# BlueESC.net
KiCad netlist of a schematic drawn in EAGLE
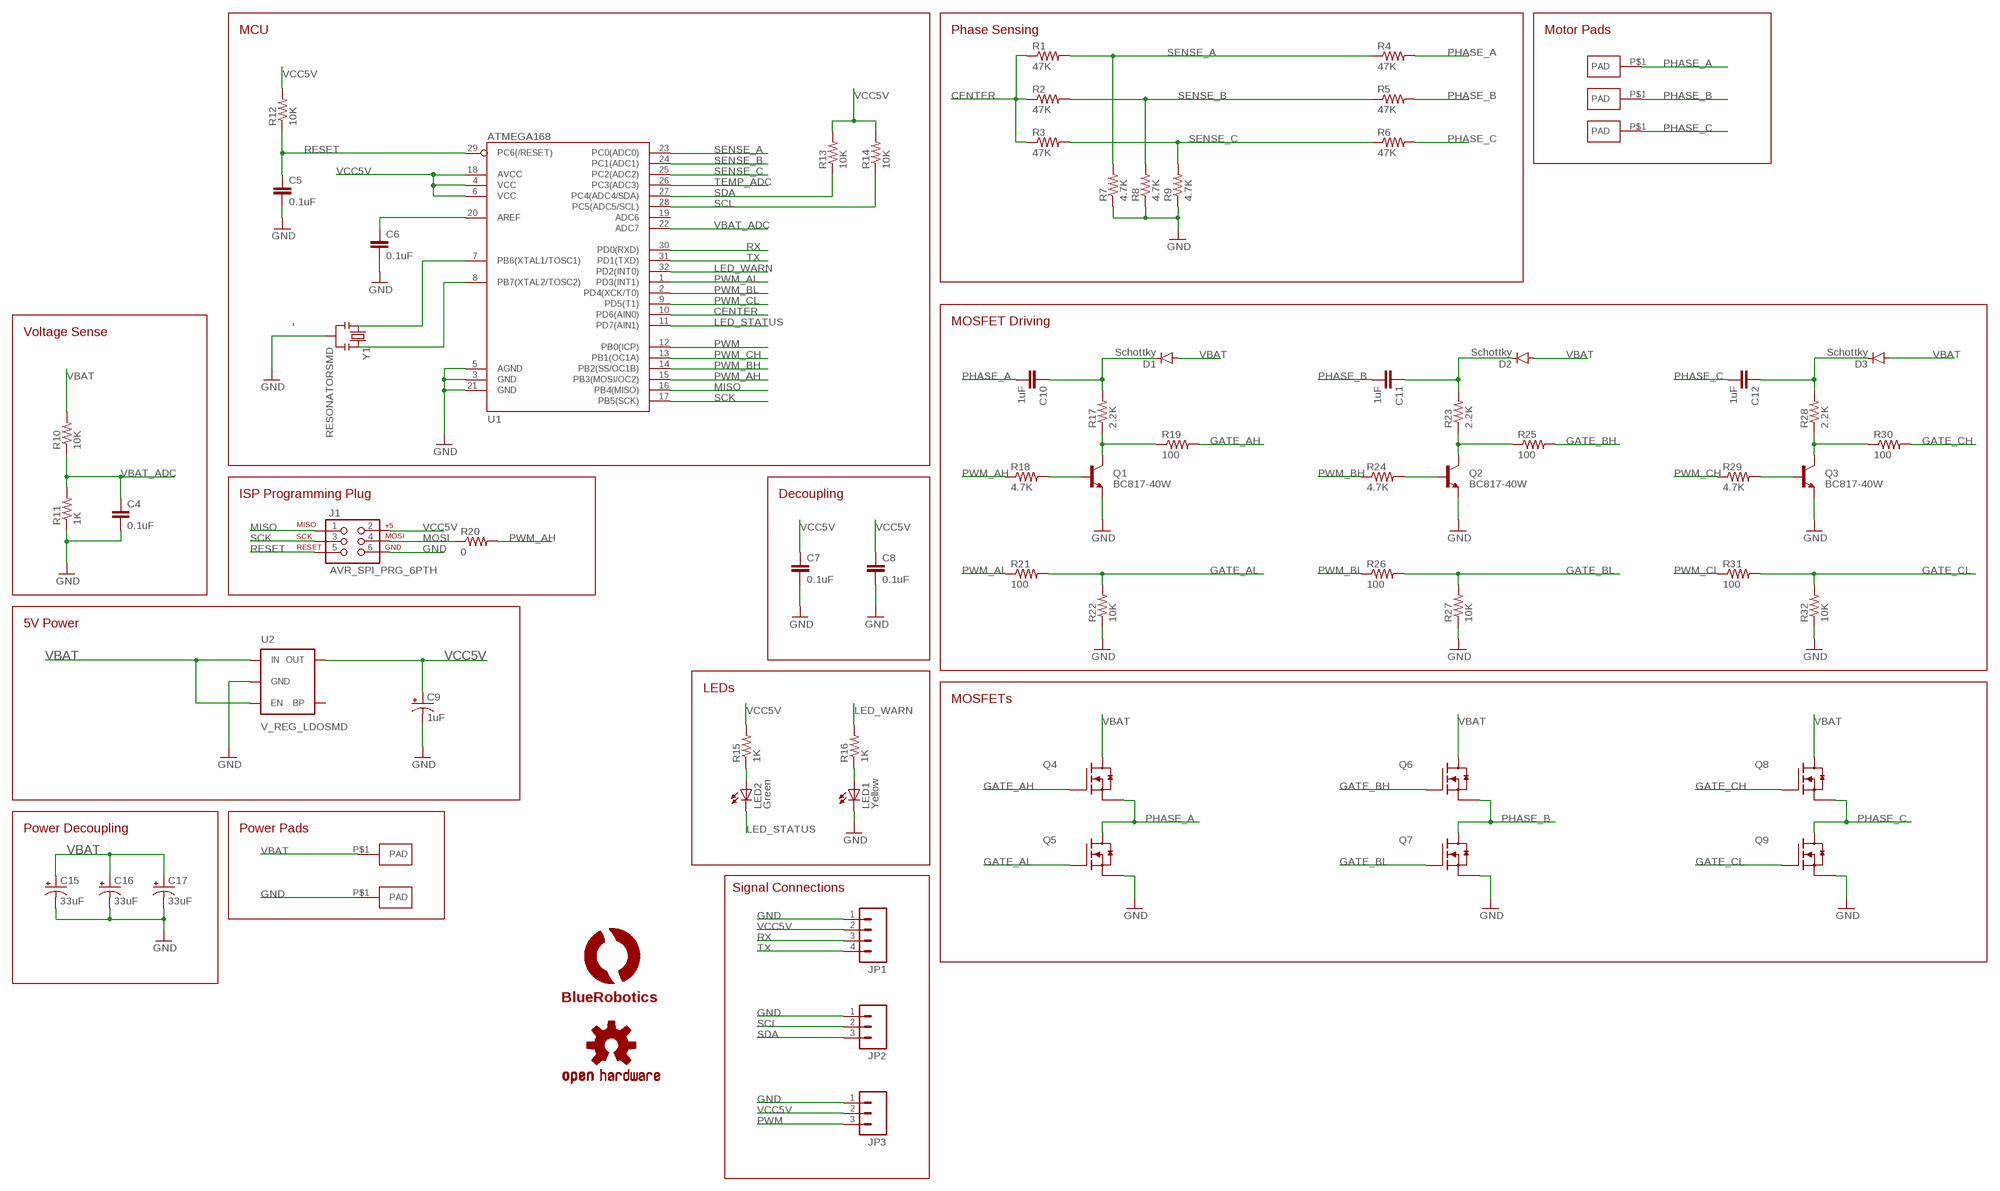
[diagram p0: schematic, sheet 1]

(export (version "E")
  (design (tool "Eeschema 10.0.6"))
  (components
    (comp (ref "C4")
      (value "0.1uF")
      (footprint "eagle-import:0603-CAP")
      (libsource (lib "eagle-import") (part "CAP0603-CAP"))
    )
    (comp (ref "C5")
      (value "0.1uF")
      (footprint "eagle-import:0603-CAP")
      (libsource (lib "eagle-import") (part "CAP0603-CAP"))
    )
    (comp (ref "C6")
      (value "0.1uF")
      (footprint "eagle-import:0603-CAP")
      (libsource (lib "eagle-import") (part "CAP0603-CAP"))
    )
    (comp (ref "C7")
      (value "0.1uF")
      (footprint "eagle-import:0603-CAP")
      (libsource (lib "eagle-import") (part "CAP0603-CAP"))
    )
    (comp (ref "C8")
      (value "0.1uF")
      (footprint "eagle-import:0603-CAP")
      (libsource (lib "eagle-import") (part "CAP0603-CAP"))
    )
    (comp (ref "C9")
      (value "1uF")
      (footprint "eagle-import:EIA3216")
      (libsource (lib "eagle-import") (part "CAP_POL1206"))
    )
    (comp (ref "C10")
      (value "1uF")
      (footprint "eagle-import:0805")
      (libsource (lib "eagle-import") (part "CAP0805"))
    )
    (comp (ref "C11")
      (value "1uF")
      (footprint "eagle-import:0805")
      (libsource (lib "eagle-import") (part "CAP0805"))
    )
    (comp (ref "C12")
      (value "1uF")
      (footprint "eagle-import:0805")
      (libsource (lib "eagle-import") (part "CAP0805"))
    )
    (comp (ref "C15")
      (value "33uF")
      (footprint "eagle-import:EIA6032")
      (libsource (lib "eagle-import") (part "CAP_POL6032"))
    )
    (comp (ref "C16")
      (value "33uF")
      (footprint "eagle-import:EIA6032")
      (libsource (lib "eagle-import") (part "CAP_POL6032"))
    )
    (comp (ref "C17")
      (value "33uF")
      (footprint "eagle-import:EIA6032")
      (libsource (lib "eagle-import") (part "CAP_POL6032"))
    )
    (comp (ref "D1")
      (value "Schottky")
      (footprint "eagle-import:SOD-323")
      (libsource (lib "eagle-import") (part "DIODESOD"))
    )
    (comp (ref "D2")
      (value "Schottky")
      (footprint "eagle-import:SOD-323")
      (libsource (lib "eagle-import") (part "DIODESOD"))
    )
    (comp (ref "D3")
      (value "Schottky")
      (footprint "eagle-import:SOD-323")
      (libsource (lib "eagle-import") (part "DIODESOD"))
    )
    (comp (ref "J1")
      (value "AVR_SPI_PRG_6PTH")
      (footprint "eagle-import:2X3")
      (libsource (lib "eagle-import") (part "AVR_SPI_PRG_6PTH"))
    )
    (comp (ref "JP1")
      (value "M04PTH")
      (footprint "eagle-import:1X04")
      (libsource (lib "eagle-import") (part "M04PTH"))
    )
    (comp (ref "JP2")
      (value "M03PTH")
      (footprint "eagle-import:1X03")
      (libsource (lib "eagle-import") (part "M03PTH"))
    )
    (comp (ref "JP3")
      (value "M03PTH")
      (footprint "eagle-import:1X03")
      (libsource (lib "eagle-import") (part "M03PTH"))
    )
    (comp (ref "LED1")
      (value "Yellow")
      (footprint "eagle-import:LED-0603")
      (libsource (lib "eagle-import") (part "LED0603"))
    )
    (comp (ref "LED2")
      (value "Green")
      (footprint "eagle-import:LED-0603")
      (libsource (lib "eagle-import") (part "LED0603"))
    )
    (comp (ref "LOGO1")
      (value "OSHW-LOGOM")
      (footprint "eagle-import:OSHW-LOGO-M")
      (libsource (lib "eagle-import") (part "OSHW-LOGOM"))
    )
    (comp (ref "Q1")
      (value "BC817-40W")
      (footprint "eagle-import:SOT23")
      (libsource (lib "eagle-import") (part "TRANSISTOR_NPNSOT23"))
    )
    (comp (ref "Q2")
      (value "BC817-40W")
      (footprint "eagle-import:SOT23")
      (libsource (lib "eagle-import") (part "TRANSISTOR_NPNSOT23"))
    )
    (comp (ref "Q3")
      (value "BC817-40W")
      (footprint "eagle-import:SOT23")
      (libsource (lib "eagle-import") (part "TRANSISTOR_NPNSOT23"))
    )
    (comp (ref "Q4")
      (value "SI7370")
      (footprint "eagle-import:POWERPAK-SO-08")
      (libsource (lib "eagle-import") (part "SI7370"))
    )
    (comp (ref "Q5")
      (value "SI7370")
      (footprint "eagle-import:POWERPAK-SO-08")
      (libsource (lib "eagle-import") (part "SI7370"))
    )
    (comp (ref "Q6")
      (value "SiR158DP")
      (footprint "eagle-import:POWERPAK-SO-08")
      (libsource (lib "eagle-import") (part "SI7370"))
    )
    (comp (ref "Q7")
      (value "SI7370")
      (footprint "eagle-import:POWERPAK-SO-08")
      (libsource (lib "eagle-import") (part "SI7370"))
    )
    (comp (ref "Q8")
      (value "SI7370")
      (footprint "eagle-import:POWERPAK-SO-08")
      (libsource (lib "eagle-import") (part "SI7370"))
    )
    (comp (ref "Q9")
      (value "SI7370")
      (footprint "eagle-import:POWERPAK-SO-08")
      (libsource (lib "eagle-import") (part "SI7370"))
    )
    (comp (ref "R1")
      (value "47K")
      (footprint "eagle-import:0603-RES")
      (libsource (lib "eagle-import") (part "33KOHM1/10W1%(0603)"))
    )
    (comp (ref "R2")
      (value "47K")
      (footprint "eagle-import:0603-RES")
      (libsource (lib "eagle-import") (part "33KOHM1/10W1%(0603)"))
    )
    (comp (ref "R3")
      (value "47K")
      (footprint "eagle-import:0603-RES")
      (libsource (lib "eagle-import") (part "33KOHM1/10W1%(0603)"))
    )
    (comp (ref "R4")
      (value "47K")
      (footprint "eagle-import:0603-RES")
      (libsource (lib "eagle-import") (part "33KOHM1/10W1%(0603)"))
    )
    (comp (ref "R5")
      (value "47K")
      (footprint "eagle-import:0603-RES")
      (libsource (lib "eagle-import") (part "33KOHM1/10W1%(0603)"))
    )
    (comp (ref "R6")
      (value "47K")
      (footprint "eagle-import:0603-RES")
      (libsource (lib "eagle-import") (part "33KOHM1/10W1%(0603)"))
    )
    (comp (ref "R7")
      (value "4.7K")
      (footprint "eagle-import:0603-RES")
      (libsource (lib "eagle-import") (part "RESISTOR0603"))
    )
    (comp (ref "R8")
      (value "4.7K")
      (footprint "eagle-import:0603-RES")
      (libsource (lib "eagle-import") (part "RESISTOR0603"))
    )
    (comp (ref "R9")
      (value "4.7K")
      (footprint "eagle-import:0603-RES")
      (libsource (lib "eagle-import") (part "RESISTOR0603"))
    )
    (comp (ref "R10")
      (value "10K")
      (footprint "eagle-import:0603-RES")
      (libsource (lib "eagle-import") (part "33KOHM1/10W1%(0603)"))
    )
    (comp (ref "R11")
      (value "1K")
      (footprint "eagle-import:0603-RES")
      (libsource (lib "eagle-import") (part "33KOHM1/10W1%(0603)"))
    )
    (comp (ref "R12")
      (value "10K")
      (footprint "eagle-import:0603-RES")
      (libsource (lib "eagle-import") (part "33KOHM1/10W1%(0603)"))
    )
    (comp (ref "R13")
      (value "10K")
      (footprint "eagle-import:0603-RES")
      (libsource (lib "eagle-import") (part "33KOHM1/10W1%(0603)"))
    )
    (comp (ref "R14")
      (value "10K")
      (footprint "eagle-import:0603-RES")
      (libsource (lib "eagle-import") (part "33KOHM1/10W1%(0603)"))
    )
    (comp (ref "R15")
      (value "1K")
      (footprint "eagle-import:0603-RES")
      (libsource (lib "eagle-import") (part "RESISTOR0603-RES"))
    )
    (comp (ref "R16")
      (value "1K")
      (footprint "eagle-import:0603-RES")
      (libsource (lib "eagle-import") (part "RESISTOR0603-RES"))
    )
    (comp (ref "R17")
      (value "2.2K")
      (footprint "eagle-import:0603-RES")
      (libsource (lib "eagle-import") (part "33KOHM1/10W1%(0603)"))
    )
    (comp (ref "R18")
      (value "4.7K")
      (footprint "eagle-import:0603-RES")
      (libsource (lib "eagle-import") (part "33KOHM1/10W1%(0603)"))
    )
    (comp (ref "R19")
      (value "100")
      (footprint "eagle-import:0603-RES")
      (libsource (lib "eagle-import") (part "33KOHM1/10W1%(0603)"))
    )
    (comp (ref "R20")
      (value "0")
      (footprint "eagle-import:0603-RES")
      (libsource (lib "eagle-import") (part "33KOHM1/10W1%(0603)"))
    )
    (comp (ref "R21")
      (value "100")
      (footprint "eagle-import:0603-RES")
      (libsource (lib "eagle-import") (part "33KOHM1/10W1%(0603)"))
    )
    (comp (ref "R22")
      (value "10K")
      (footprint "eagle-import:0603-RES")
      (libsource (lib "eagle-import") (part "33KOHM1/10W1%(0603)"))
    )
    (comp (ref "R23")
      (value "2.2K")
      (footprint "eagle-import:0603-RES")
      (libsource (lib "eagle-import") (part "33KOHM1/10W1%(0603)"))
    )
    (comp (ref "R24")
      (value "4.7K")
      (footprint "eagle-import:0603-RES")
      (libsource (lib "eagle-import") (part "33KOHM1/10W1%(0603)"))
    )
    (comp (ref "R25")
      (value "100")
      (footprint "eagle-import:0603-RES")
      (libsource (lib "eagle-import") (part "33KOHM1/10W1%(0603)"))
    )
    (comp (ref "R26")
      (value "100")
      (footprint "eagle-import:0603-RES")
      (libsource (lib "eagle-import") (part "33KOHM1/10W1%(0603)"))
    )
    (comp (ref "R27")
      (value "10K")
      (footprint "eagle-import:0603-RES")
      (libsource (lib "eagle-import") (part "33KOHM1/10W1%(0603)"))
    )
    (comp (ref "R28")
      (value "2.2K")
      (footprint "eagle-import:0603-RES")
      (libsource (lib "eagle-import") (part "33KOHM1/10W1%(0603)"))
    )
    (comp (ref "R29")
      (value "4.7K")
      (footprint "eagle-import:0603-RES")
      (libsource (lib "eagle-import") (part "33KOHM1/10W1%(0603)"))
    )
    (comp (ref "R30")
      (value "100")
      (footprint "eagle-import:0603-RES")
      (libsource (lib "eagle-import") (part "33KOHM1/10W1%(0603)"))
    )
    (comp (ref "R31")
      (value "100")
      (footprint "eagle-import:0603-RES")
      (libsource (lib "eagle-import") (part "33KOHM1/10W1%(0603)"))
    )
    (comp (ref "R32")
      (value "10K")
      (footprint "eagle-import:0603-RES")
      (libsource (lib "eagle-import") (part "33KOHM1/10W1%(0603)"))
    )
    (comp (ref "U$1")
      (value "PADLARGE-ONE-SIDE")
      (footprint "eagle-import:PAD-0.2X0.3-ONE-SIDE")
      (libsource (lib "eagle-import") (part "PADLARGE-ONE-SIDE"))
    )
    (comp (ref "U$2")
      (value "PADLARGE-ONE-SIDE")
      (footprint "eagle-import:PAD-0.2X0.3-ONE-SIDE")
      (libsource (lib "eagle-import") (part "PADLARGE-ONE-SIDE"))
    )
    (comp (ref "U$3")
      (value "PADLARGE-ONE-SIDE")
      (footprint "eagle-import:PAD-0.2X0.3-ONE-SIDE")
      (libsource (lib "eagle-import") (part "PADLARGE-ONE-SIDE"))
    )
    (comp (ref "U$4")
      (value "LOGOBR-LOGO-M")
      (footprint "eagle-import:BR-LOGO-MEDIUM")
      (libsource (lib "eagle-import") (part "LOGOBR-LOGO-M"))
    )
    (comp (ref "U$13")
      (value "PADLARGE-ONE-SIDE")
      (footprint "eagle-import:PAD-0.2X0.3-ONE-SIDE")
      (libsource (lib "eagle-import") (part "PADLARGE-ONE-SIDE"))
    )
    (comp (ref "U$14")
      (value "PADLARGE-ONE-SIDE")
      (footprint "eagle-import:PAD-0.2X0.3-ONE-SIDE")
      (libsource (lib "eagle-import") (part "PADLARGE-ONE-SIDE"))
    )
    (comp (ref "U1")
      (value "ATMEGA168")
      (footprint "eagle-import:TQFP32-08")
      (libsource (lib "eagle-import") (part "ATMEGA168"))
    )
    (comp (ref "U2")
      (value "V_REG_LDOSMD")
      (footprint "eagle-import:SOT23-5")
      (libsource (lib "eagle-import") (part "V_REG_LDOSMD"))
    )
    (comp (ref "Y1")
      (value "RESONATORSMD")
      (footprint "eagle-import:RESONATOR-SMD")
      (libsource (lib "eagle-import") (part "RESONATORSMD"))
    )
  )
  (nets
    (net (code "1") (name "/CENTER") (class "Default")
      (node (ref "R1") (pin "1") (pinfunction "1_1") (pintype "passive"))
      (node (ref "R2") (pin "1") (pinfunction "1_1") (pintype "passive"))
      (node (ref "R3") (pin "1") (pinfunction "1_1") (pintype "passive"))
      (node (ref "U1") (pin "10") (pinfunction "PD6(AIN0)_10") (pintype "bidirectional"))
    )
    (net (code "2") (name "/GATE_AH") (class "Default")
      (node (ref "Q4") (pin "4") (pinfunction "G_4") (pintype "passive"))
      (node (ref "R19") (pin "2") (pinfunction "2_2") (pintype "passive"))
    )
    (net (code "3") (name "/GATE_AL") (class "Default")
      (node (ref "Q5") (pin "4") (pinfunction "G_4") (pintype "passive"))
      (node (ref "R21") (pin "2") (pinfunction "2_2") (pintype "passive"))
      (node (ref "R22") (pin "2") (pinfunction "2_2") (pintype "passive"))
    )
    (net (code "4") (name "/GATE_BH") (class "Default")
      (node (ref "Q6") (pin "4") (pinfunction "G_4") (pintype "passive"))
      (node (ref "R25") (pin "2") (pinfunction "2_2") (pintype "passive"))
    )
    (net (code "5") (name "/GATE_BL") (class "Default")
      (node (ref "Q7") (pin "4") (pinfunction "G_4") (pintype "passive"))
      (node (ref "R26") (pin "2") (pinfunction "2_2") (pintype "passive"))
      (node (ref "R27") (pin "2") (pinfunction "2_2") (pintype "passive"))
    )
    (net (code "6") (name "/GATE_CH") (class "Default")
      (node (ref "Q8") (pin "4") (pinfunction "G_4") (pintype "passive"))
      (node (ref "R30") (pin "2") (pinfunction "2_2") (pintype "passive"))
    )
    (net (code "7") (name "/GATE_CL") (class "Default")
      (node (ref "Q9") (pin "4") (pinfunction "G_4") (pintype "passive"))
      (node (ref "R31") (pin "2") (pinfunction "2_2") (pintype "passive"))
      (node (ref "R32") (pin "2") (pinfunction "2_2") (pintype "passive"))
    )
    (net (code "8") (name "/LED_STATUS") (class "Default")
      (node (ref "LED2") (pin "C") (pinfunction "C_C") (pintype "passive"))
      (node (ref "U1") (pin "11") (pinfunction "PD7(AIN1)_11") (pintype "bidirectional"))
    )
    (net (code "9") (name "/LED_WARN") (class "Default")
      (node (ref "R16") (pin "2") (pinfunction "2_2") (pintype "passive"))
      (node (ref "U1") (pin "32") (pinfunction "PD2(INT0)_32") (pintype "bidirectional"))
    )
    (net (code "10") (name "/MISO") (class "Default")
      (node (ref "J1") (pin "1") (pinfunction "1_1") (pintype "passive"))
      (node (ref "U1") (pin "16") (pinfunction "PB4(MISO)_16") (pintype "bidirectional"))
    )
    (net (code "11") (name "/MOSI") (class "Default")
      (node (ref "J1") (pin "4") (pinfunction "4_4") (pintype "passive"))
      (node (ref "R20") (pin "1") (pinfunction "1_1") (pintype "passive"))
    )
    (net (code "12") (name "/PHASE_A") (class "Default")
      (node (ref "C10") (pin "2") (pinfunction "2_2") (pintype "passive"))
      (node (ref "Q4") (pin "3") (pinfunction "S3_3") (pintype "passive"))
      (node (ref "Q5") (pin "5-8") (pinfunction "D_5-8") (pintype "passive"))
      (node (ref "R4") (pin "2") (pinfunction "2_2") (pintype "passive"))
      (node (ref "U$13") (pin "P$1") (pinfunction "PAD_P$1") (pintype "bidirectional"))
    )
    (net (code "13") (name "/PHASE_B") (class "Default")
      (node (ref "C11") (pin "2") (pinfunction "2_2") (pintype "passive"))
      (node (ref "Q6") (pin "3") (pinfunction "S3_3") (pintype "passive"))
      (node (ref "Q7") (pin "5-8") (pinfunction "D_5-8") (pintype "passive"))
      (node (ref "R5") (pin "2") (pinfunction "2_2") (pintype "passive"))
      (node (ref "U$14") (pin "P$1") (pinfunction "PAD_P$1") (pintype "bidirectional"))
    )
    (net (code "14") (name "/PHASE_C") (class "Default")
      (node (ref "C12") (pin "2") (pinfunction "2_2") (pintype "passive"))
      (node (ref "Q8") (pin "3") (pinfunction "S3_3") (pintype "passive"))
      (node (ref "Q9") (pin "5-8") (pinfunction "D_5-8") (pintype "passive"))
      (node (ref "R6") (pin "2") (pinfunction "2_2") (pintype "passive"))
      (node (ref "U$1") (pin "P$1") (pinfunction "PAD_P$1") (pintype "bidirectional"))
    )
    (net (code "15") (name "/PWM") (class "Default")
      (node (ref "JP3") (pin "3") (pinfunction "3_3") (pintype "passive"))
      (node (ref "U1") (pin "12") (pinfunction "PB0(ICP)_12") (pintype "bidirectional"))
    )
    (net (code "16") (name "/PWM_AH") (class "Default")
      (node (ref "R18") (pin "1") (pinfunction "1_1") (pintype "passive"))
      (node (ref "R20") (pin "2") (pinfunction "2_2") (pintype "passive"))
      (node (ref "U1") (pin "15") (pinfunction "PB3(MOSI/OC2)_15") (pintype "bidirectional"))
    )
    (net (code "17") (name "/PWM_AL") (class "Default")
      (node (ref "R21") (pin "1") (pinfunction "1_1") (pintype "passive"))
      (node (ref "U1") (pin "1") (pinfunction "PD3(INT1)_1") (pintype "bidirectional"))
    )
    (net (code "18") (name "/PWM_BH") (class "Default")
      (node (ref "R24") (pin "1") (pinfunction "1_1") (pintype "passive"))
      (node (ref "U1") (pin "14") (pinfunction "PB2(SS/OC1B)_14") (pintype "bidirectional"))
    )
    (net (code "19") (name "/PWM_BL") (class "Default")
      (node (ref "R26") (pin "1") (pinfunction "1_1") (pintype "passive"))
      (node (ref "U1") (pin "2") (pinfunction "PD4(XCK/T0)_2") (pintype "bidirectional"))
    )
    (net (code "20") (name "/PWM_CH") (class "Default")
      (node (ref "R29") (pin "1") (pinfunction "1_1") (pintype "passive"))
      (node (ref "U1") (pin "13") (pinfunction "PB1(OC1A)_13") (pintype "bidirectional"))
    )
    (net (code "21") (name "/PWM_CL") (class "Default")
      (node (ref "R31") (pin "1") (pinfunction "1_1") (pintype "passive"))
      (node (ref "U1") (pin "9") (pinfunction "PD5(T1)_9") (pintype "bidirectional"))
    )
    (net (code "22") (name "/RESET") (class "Default")
      (node (ref "C5") (pin "1") (pinfunction "1_1") (pintype "passive"))
      (node (ref "J1") (pin "5") (pinfunction "5_5") (pintype "passive"))
      (node (ref "R12") (pin "1") (pinfunction "1_1") (pintype "passive"))
      (node (ref "U1") (pin "29") (pinfunction "PC6(/RESET)_29") (pintype "bidirectional"))
    )
    (net (code "23") (name "/RX") (class "Default")
      (node (ref "JP1") (pin "3") (pinfunction "3_3") (pintype "passive"))
      (node (ref "U1") (pin "30") (pinfunction "PD0(RXD)_30") (pintype "bidirectional"))
    )
    (net (code "24") (name "/SCK") (class "Default")
      (node (ref "J1") (pin "3") (pinfunction "3_3") (pintype "passive"))
      (node (ref "U1") (pin "17") (pinfunction "PB5(SCK)_17") (pintype "bidirectional"))
    )
    (net (code "25") (name "/SCL") (class "Default")
      (node (ref "JP2") (pin "2") (pinfunction "2_2") (pintype "passive"))
      (node (ref "R14") (pin "1") (pinfunction "1_1") (pintype "passive"))
      (node (ref "U1") (pin "28") (pinfunction "PC5(ADC5/SCL)_28") (pintype "bidirectional"))
    )
    (net (code "26") (name "/SDA") (class "Default")
      (node (ref "JP2") (pin "3") (pinfunction "3_3") (pintype "passive"))
      (node (ref "R13") (pin "1") (pinfunction "1_1") (pintype "passive"))
      (node (ref "U1") (pin "27") (pinfunction "PC4(ADC4/SDA)_27") (pintype "bidirectional"))
    )
    (net (code "27") (name "/SENSE_A") (class "Default")
      (node (ref "R1") (pin "2") (pinfunction "2_2") (pintype "passive"))
      (node (ref "R4") (pin "1") (pinfunction "1_1") (pintype "passive"))
      (node (ref "R7") (pin "2") (pinfunction "2_2") (pintype "passive"))
      (node (ref "U1") (pin "23") (pinfunction "PC0(ADC0)_23") (pintype "bidirectional"))
    )
    (net (code "28") (name "/SENSE_B") (class "Default")
      (node (ref "R2") (pin "2") (pinfunction "2_2") (pintype "passive"))
      (node (ref "R5") (pin "1") (pinfunction "1_1") (pintype "passive"))
      (node (ref "R8") (pin "2") (pinfunction "2_2") (pintype "passive"))
      (node (ref "U1") (pin "24") (pinfunction "PC1(ADC1)_24") (pintype "bidirectional"))
    )
    (net (code "29") (name "/SENSE_C") (class "Default")
      (node (ref "R3") (pin "2") (pinfunction "2_2") (pintype "passive"))
      (node (ref "R6") (pin "1") (pinfunction "1_1") (pintype "passive"))
      (node (ref "R9") (pin "2") (pinfunction "2_2") (pintype "passive"))
      (node (ref "U1") (pin "25") (pinfunction "PC2(ADC2)_25") (pintype "bidirectional"))
    )
    (net (code "30") (name "/TEMP_ADC") (class "Default")
      (node (ref "U1") (pin "26") (pinfunction "PC3(ADC3)_26") (pintype "bidirectional"))
    )
    (net (code "31") (name "/TX") (class "Default")
      (node (ref "JP1") (pin "4") (pinfunction "4_4") (pintype "passive"))
      (node (ref "U1") (pin "31") (pinfunction "PD1(TXD)_31") (pintype "bidirectional"))
    )
    (net (code "32") (name "/VBAT") (class "Default")
      (node (ref "C15") (pin "P$1") (pinfunction "+_P$1") (pintype "passive"))
      (node (ref "C16") (pin "P$1") (pinfunction "+_P$1") (pintype "passive"))
      (node (ref "C17") (pin "P$1") (pinfunction "+_P$1") (pintype "passive"))
      (node (ref "D1") (pin "A") (pinfunction "A_A") (pintype "passive"))
      (node (ref "D2") (pin "A") (pinfunction "A_A") (pintype "passive"))
      (node (ref "D3") (pin "A") (pinfunction "A_A") (pintype "passive"))
      (node (ref "Q4") (pin "5-8") (pinfunction "D_5-8") (pintype "passive"))
      (node (ref "Q6") (pin "5-8") (pinfunction "D_5-8") (pintype "passive"))
      (node (ref "Q8") (pin "5-8") (pinfunction "D_5-8") (pintype "passive"))
      (node (ref "R10") (pin "2") (pinfunction "2_2") (pintype "passive"))
      (node (ref "U$2") (pin "P$1") (pinfunction "PAD_P$1") (pintype "bidirectional"))
      (node (ref "U2") (pin "1") (pinfunction "IN_1") (pintype "input"))
      (node (ref "U2") (pin "3") (pinfunction "EN_3") (pintype "input"))
    )
    (net (code "33") (name "/VBAT_ADC") (class "Default")
      (node (ref "C4") (pin "1") (pinfunction "1_1") (pintype "passive"))
      (node (ref "R10") (pin "1") (pinfunction "1_1") (pintype "passive"))
      (node (ref "R11") (pin "2") (pinfunction "2_2") (pintype "passive"))
      (node (ref "U1") (pin "22") (pinfunction "ADC7_22") (pintype "bidirectional"))
    )
    (net (code "34") (name "/VCC5V") (class "Default")
      (node (ref "C7") (pin "1") (pinfunction "1_1") (pintype "passive"))
      (node (ref "C8") (pin "1") (pinfunction "1_1") (pintype "passive"))
      (node (ref "C9") (pin "A") (pinfunction "+_A") (pintype "passive"))
      (node (ref "J1") (pin "2") (pinfunction "2_2") (pintype "passive"))
      (node (ref "JP1") (pin "2") (pinfunction "2_2") (pintype "passive"))
      (node (ref "JP3") (pin "2") (pinfunction "2_2") (pintype "passive"))
      (node (ref "R12") (pin "2") (pinfunction "2_2") (pintype "passive"))
      (node (ref "R13") (pin "2") (pinfunction "2_2") (pintype "passive"))
      (node (ref "R14") (pin "2") (pinfunction "2_2") (pintype "passive"))
      (node (ref "R15") (pin "2") (pinfunction "2_2") (pintype "passive"))
      (node (ref "U1") (pin "18") (pinfunction "AVCC_18") (pintype "bidirectional"))
      (node (ref "U1") (pin "4") (pinfunction "VCC_4") (pintype "bidirectional"))
      (node (ref "U1") (pin "6") (pinfunction "VCC_6") (pintype "bidirectional"))
      (node (ref "U2") (pin "5") (pinfunction "OUT_5") (pintype "passive"))
    )
    (net (code "35") (name "GND") (class "Default")
      (node (ref "C15") (pin "P$2") (pinfunction "-_P$2") (pintype "passive"))
      (node (ref "C16") (pin "P$2") (pinfunction "-_P$2") (pintype "passive"))
      (node (ref "C17") (pin "P$2") (pinfunction "-_P$2") (pintype "passive"))
      (node (ref "C4") (pin "2") (pinfunction "2_2") (pintype "passive"))
      (node (ref "C5") (pin "2") (pinfunction "2_2") (pintype "passive"))
      (node (ref "C6") (pin "2") (pinfunction "2_2") (pintype "passive"))
      (node (ref "C7") (pin "2") (pinfunction "2_2") (pintype "passive"))
      (node (ref "C8") (pin "2") (pinfunction "2_2") (pintype "passive"))
      (node (ref "C9") (pin "C") (pinfunction "-_C") (pintype "passive"))
      (node (ref "J1") (pin "6") (pinfunction "6_6") (pintype "passive"))
      (node (ref "JP1") (pin "1") (pinfunction "1_1") (pintype "passive"))
      (node (ref "JP2") (pin "1") (pinfunction "1_1") (pintype "passive"))
      (node (ref "JP3") (pin "1") (pinfunction "1_1") (pintype "passive"))
      (node (ref "LED1") (pin "C") (pinfunction "C_C") (pintype "passive"))
      (node (ref "Q1") (pin "2") (pinfunction "E_2") (pintype "passive"))
      (node (ref "Q2") (pin "2") (pinfunction "E_2") (pintype "passive"))
      (node (ref "Q3") (pin "2") (pinfunction "E_2") (pintype "passive"))
      (node (ref "Q5") (pin "3") (pinfunction "S3_3") (pintype "passive"))
      (node (ref "Q7") (pin "3") (pinfunction "S3_3") (pintype "passive"))
      (node (ref "Q9") (pin "3") (pinfunction "S3_3") (pintype "passive"))
      (node (ref "R11") (pin "1") (pinfunction "1_1") (pintype "passive"))
      (node (ref "R22") (pin "1") (pinfunction "1_1") (pintype "passive"))
      (node (ref "R27") (pin "1") (pinfunction "1_1") (pintype "passive"))
      (node (ref "R32") (pin "1") (pinfunction "1_1") (pintype "passive"))
      (node (ref "R7") (pin "1") (pinfunction "1_1") (pintype "passive"))
      (node (ref "R8") (pin "1") (pinfunction "1_1") (pintype "passive"))
      (node (ref "R9") (pin "1") (pinfunction "1_1") (pintype "passive"))
      (node (ref "U$3") (pin "P$1") (pinfunction "PAD_P$1") (pintype "bidirectional"))
      (node (ref "U1") (pin "21") (pinfunction "GND_21") (pintype "bidirectional"))
      (node (ref "U1") (pin "3") (pinfunction "GND_3") (pintype "bidirectional"))
      (node (ref "U1") (pin "5") (pinfunction "AGND_5") (pintype "bidirectional"))
      (node (ref "U2") (pin "2") (pinfunction "GND_2") (pintype "input"))
      (node (ref "Y1") (pin "2") (pinfunction "2_2") (pintype "passive"))
    )
    (net (code "36") (name "Net-(C10-Pad1)") (class "Default")
      (node (ref "C10") (pin "1") (pinfunction "1_1") (pintype "passive"))
      (node (ref "D1") (pin "C") (pinfunction "C_C") (pintype "passive"))
      (node (ref "R17") (pin "2") (pinfunction "2_2") (pintype "passive"))
    )
    (net (code "37") (name "Net-(C11-Pad1)") (class "Default")
      (node (ref "C11") (pin "1") (pinfunction "1_1") (pintype "passive"))
      (node (ref "D2") (pin "C") (pinfunction "C_C") (pintype "passive"))
      (node (ref "R23") (pin "2") (pinfunction "2_2") (pintype "passive"))
    )
    (net (code "38") (name "Net-(C12-Pad1)") (class "Default")
      (node (ref "C12") (pin "1") (pinfunction "1_1") (pintype "passive"))
      (node (ref "D3") (pin "C") (pinfunction "C_C") (pintype "passive"))
      (node (ref "R28") (pin "2") (pinfunction "2_2") (pintype "passive"))
    )
    (net (code "39") (name "Net-(LED1-PadA)") (class "Default")
      (node (ref "LED1") (pin "A") (pinfunction "A_A") (pintype "passive"))
      (node (ref "R16") (pin "1") (pinfunction "1_1") (pintype "passive"))
    )
    (net (code "40") (name "Net-(LED2-PadA)") (class "Default")
      (node (ref "LED2") (pin "A") (pinfunction "A_A") (pintype "passive"))
      (node (ref "R15") (pin "1") (pinfunction "1_1") (pintype "passive"))
    )
    (net (code "41") (name "Net-(Q1-B)") (class "Default")
      (node (ref "Q1") (pin "1") (pinfunction "B_1") (pintype "passive"))
      (node (ref "R18") (pin "2") (pinfunction "2_2") (pintype "passive"))
    )
    (net (code "42") (name "Net-(Q1-C)") (class "Default")
      (node (ref "Q1") (pin "3") (pinfunction "C_3") (pintype "passive"))
      (node (ref "R17") (pin "1") (pinfunction "1_1") (pintype "passive"))
      (node (ref "R19") (pin "1") (pinfunction "1_1") (pintype "passive"))
    )
    (net (code "43") (name "Net-(Q2-B)") (class "Default")
      (node (ref "Q2") (pin "1") (pinfunction "B_1") (pintype "passive"))
      (node (ref "R24") (pin "2") (pinfunction "2_2") (pintype "passive"))
    )
    (net (code "44") (name "Net-(Q2-C)") (class "Default")
      (node (ref "Q2") (pin "3") (pinfunction "C_3") (pintype "passive"))
      (node (ref "R23") (pin "1") (pinfunction "1_1") (pintype "passive"))
      (node (ref "R25") (pin "1") (pinfunction "1_1") (pintype "passive"))
    )
    (net (code "45") (name "Net-(Q3-B)") (class "Default")
      (node (ref "Q3") (pin "1") (pinfunction "B_1") (pintype "passive"))
      (node (ref "R29") (pin "2") (pinfunction "2_2") (pintype "passive"))
    )
    (net (code "46") (name "Net-(Q3-C)") (class "Default")
      (node (ref "Q3") (pin "3") (pinfunction "C_3") (pintype "passive"))
      (node (ref "R28") (pin "1") (pinfunction "1_1") (pintype "passive"))
      (node (ref "R30") (pin "1") (pinfunction "1_1") (pintype "passive"))
    )
    (net (code "47") (name "Net-(U1-AREF)") (class "Default")
      (node (ref "C6") (pin "1") (pinfunction "1_1") (pintype "passive"))
      (node (ref "U1") (pin "20") (pinfunction "AREF_20") (pintype "bidirectional"))
    )
    (net (code "48") (name "Net-(U1-PB6(XTAL1{slash}TOSC1))") (class "Default")
      (node (ref "U1") (pin "7") (pinfunction "PB6(XTAL1/TOSC1)_7") (pintype "bidirectional"))
      (node (ref "Y1") (pin "1") (pinfunction "1_1") (pintype "passive"))
    )
    (net (code "49") (name "Net-(U1-PB7(XTAL2{slash}TOSC2))") (class "Default")
      (node (ref "U1") (pin "8") (pinfunction "PB7(XTAL2/TOSC2)_8") (pintype "bidirectional"))
      (node (ref "Y1") (pin "3") (pinfunction "3_3") (pintype "passive"))
    )
    (net (code "50") (name "unconnected-(Q4-S1-Pad1)") (class "Default")
      (node (ref "Q4") (pin "1") (pinfunction "S1_1") (pintype "passive"))
    )
    (net (code "51") (name "unconnected-(Q4-S2-Pad2)") (class "Default")
      (node (ref "Q4") (pin "2") (pinfunction "S2_2") (pintype "passive"))
    )
    (net (code "52") (name "unconnected-(Q5-S1-Pad1)") (class "Default")
      (node (ref "Q5") (pin "1") (pinfunction "S1_1") (pintype "passive"))
    )
    (net (code "53") (name "unconnected-(Q5-S2-Pad2)") (class "Default")
      (node (ref "Q5") (pin "2") (pinfunction "S2_2") (pintype "passive"))
    )
    (net (code "54") (name "unconnected-(Q6-S1-Pad1)") (class "Default")
      (node (ref "Q6") (pin "1") (pinfunction "S1_1") (pintype "passive"))
    )
    (net (code "55") (name "unconnected-(Q6-S2-Pad2)") (class "Default")
      (node (ref "Q6") (pin "2") (pinfunction "S2_2") (pintype "passive"))
    )
    (net (code "56") (name "unconnected-(Q7-S1-Pad1)") (class "Default")
      (node (ref "Q7") (pin "1") (pinfunction "S1_1") (pintype "passive"))
    )
    (net (code "57") (name "unconnected-(Q7-S2-Pad2)") (class "Default")
      (node (ref "Q7") (pin "2") (pinfunction "S2_2") (pintype "passive"))
    )
    (net (code "58") (name "unconnected-(Q8-S1-Pad1)") (class "Default")
      (node (ref "Q8") (pin "1") (pinfunction "S1_1") (pintype "passive"))
    )
    (net (code "59") (name "unconnected-(Q8-S2-Pad2)") (class "Default")
      (node (ref "Q8") (pin "2") (pinfunction "S2_2") (pintype "passive"))
    )
    (net (code "60") (name "unconnected-(Q9-S1-Pad1)") (class "Default")
      (node (ref "Q9") (pin "1") (pinfunction "S1_1") (pintype "passive"))
    )
    (net (code "61") (name "unconnected-(Q9-S2-Pad2)") (class "Default")
      (node (ref "Q9") (pin "2") (pinfunction "S2_2") (pintype "passive"))
    )
    (net (code "62") (name "unconnected-(U1-ADC6-Pad19)") (class "Default")
      (node (ref "U1") (pin "19") (pinfunction "ADC6_19") (pintype "bidirectional"))
    )
    (net (code "63") (name "unconnected-(U2-BP-Pad4)") (class "Default")
      (node (ref "U2") (pin "4") (pinfunction "BP_4") (pintype "input"))
    )
  )
)
